# TrinketBlinkM0H.net
KiCad netlist of a schematic drawn in EAGLE
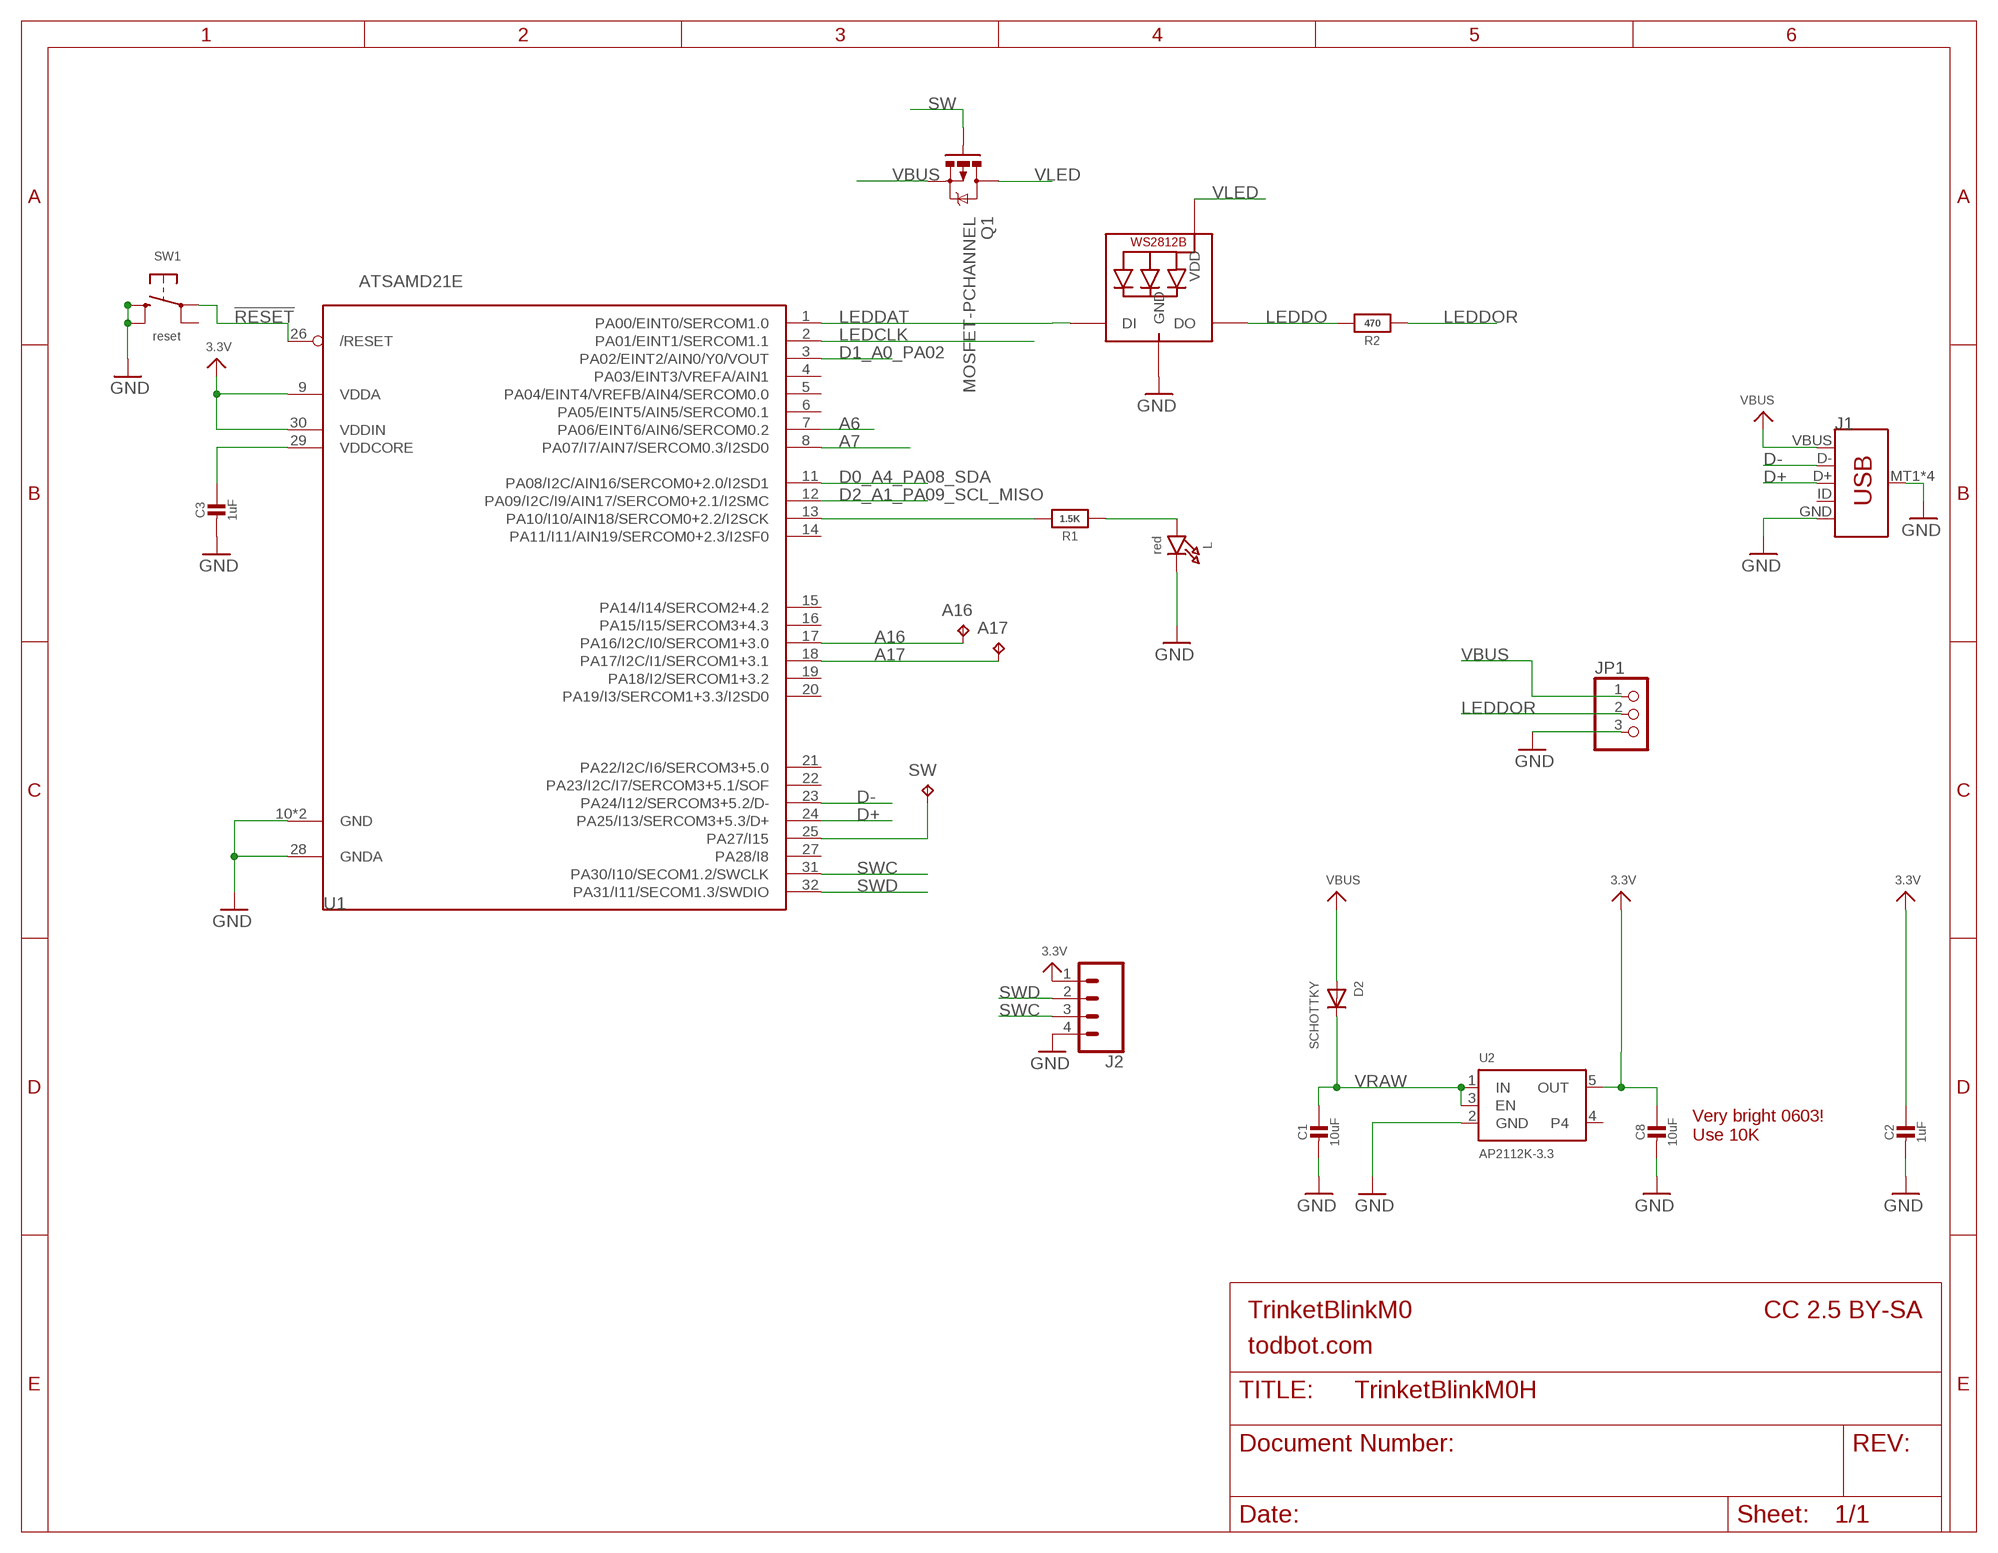
[diagram p0: schematic, sheet 1]

(export (version "E")
  (design (tool "Eeschema 10.0.6"))
  (components
    (comp (ref "A16")
      (value "TPB1,27")
      (footprint "eagle-import:B1,27")
      (libsource (lib "eagle-import") (part "TPB1,27"))
    )
    (comp (ref "A17")
      (value "TPB1,27")
      (footprint "eagle-import:B1,27")
      (libsource (lib "eagle-import") (part "TPB1,27"))
    )
    (comp (ref "C1")
      (value "10uF")
      (footprint "eagle-import:0805-NO")
      (libsource (lib "eagle-import") (part "CAP_CERAMIC0805-NOOUTLINE"))
    )
    (comp (ref "C2")
      (value "1uF")
      (footprint "eagle-import:0603-NO")
      (libsource (lib "eagle-import") (part "CAP_CERAMIC0603_NO"))
    )
    (comp (ref "C3")
      (value "1uF")
      (footprint "eagle-import:0603-NO")
      (libsource (lib "eagle-import") (part "CAP_CERAMIC0603_NO"))
    )
    (comp (ref "C8")
      (value "10uF")
      (footprint "eagle-import:0805-NO")
      (libsource (lib "eagle-import") (part "CAP_CERAMIC0805-NOOUTLINE"))
    )
    (comp (ref "D2")
      (value "SCHOTTKY")
      (footprint "eagle-import:SOD-123FL")
      (libsource (lib "eagle-import") (part "DIODE_SOD-123FL"))
    )
    (comp (ref "J1")
      (value "USB_MICRO-B_SMT")
      (footprint "eagle-import:USB-MICROB")
      (libsource (lib "eagle-import") (part "USB_MICRO-B_SMT"))
    )
    (comp (ref "J2")
      (value "CONN_04")
      (footprint "eagle-import:1X04")
      (libsource (lib "eagle-import") (part "CONN_04"))
    )
    (comp (ref "JP1")
      (value "PINHD-1X3CB")
      (footprint "eagle-import:1X03-CLEANBIG")
      (libsource (lib "eagle-import") (part "PINHD-1X3CB"))
    )
    (comp (ref "L")
      (value "red")
      (footprint "eagle-import:CHIPLED_0603_NOOUTLINE")
      (libsource (lib "eagle-import") (part "LED0603_NOOUTLINE"))
    )
    (comp (ref "LED1")
      (value "WS2812B_5050N")
      (footprint "eagle-import:WS2812B-NARROW")
      (libsource (lib "eagle-import") (part "WS2812B_5050N"))
    )
    (comp (ref "Q1")
      (value "MOSFET-PCHANNEL")
      (footprint "eagle-import:SOT23-3")
      (libsource (lib "eagle-import") (part "MOSFET-PCHANNEL"))
    )
    (comp (ref "R1")
      (value "1.5K")
      (footprint "eagle-import:0603-NO")
      (libsource (lib "eagle-import") (part "RESISTOR_0603_NOOUT"))
    )
    (comp (ref "R2")
      (value "470")
      (footprint "eagle-import:0603-NO")
      (libsource (lib "eagle-import") (part "RESISTOR_0603_NOOUT"))
    )
    (comp (ref "SW")
      (value "TPB1,27")
      (footprint "eagle-import:B1,27")
      (libsource (lib "eagle-import") (part "TPB1,27"))
    )
    (comp (ref "SW1")
      (value "reset")
      (footprint "eagle-import:BTN_KMR2_4.6X2.8")
      (libsource (lib "eagle-import") (part "SWITCH_TACT_SMT4.6X2.8"))
    )
    (comp (ref "U1")
      (value "ATSAMD21E")
      (footprint "eagle-import:QFN32_5MM")
      (libsource (lib "eagle-import") (part "ATSAMD21E"))
    )
    (comp (ref "U2")
      (value "AP2112K-3.3")
      (footprint "eagle-import:SOT23-5")
      (libsource (lib "eagle-import") (part "VREG_SOT23-5"))
    )
  )
  (nets
    (net (code "1") (name "/A6") (class "Default")
      (node (ref "U1") (pin "7") (pinfunction "PA06/EINT6/AIN6/SERCOM0.2_7") (pintype "bidirectional"))
    )
    (net (code "2") (name "/A7") (class "Default")
      (node (ref "U1") (pin "8") (pinfunction "PA07/I7/AIN7/SERCOM0.3/I2SD0_8") (pintype "bidirectional"))
    )
    (net (code "3") (name "/A16") (class "Default")
      (node (ref "A16") (pin "TP") (pinfunction "TP_TP") (pintype "input"))
      (node (ref "U1") (pin "17") (pinfunction "PA16/I2C/I0/SERCOM1+3.0_17") (pintype "bidirectional"))
    )
    (net (code "4") (name "/A17") (class "Default")
      (node (ref "A17") (pin "TP") (pinfunction "TP_TP") (pintype "input"))
      (node (ref "U1") (pin "18") (pinfunction "PA17/I2C/I1/SERCOM1+3.1_18") (pintype "bidirectional"))
    )
    (net (code "5") (name "/D+") (class "Default")
      (node (ref "J1") (pin "D+") (pinfunction "D+_D+") (pintype "bidirectional"))
      (node (ref "U1") (pin "24") (pinfunction "PA25/I13/SERCOM3+5.3/D+_24") (pintype "bidirectional"))
    )
    (net (code "6") (name "/D-") (class "Default")
      (node (ref "J1") (pin "D-") (pinfunction "D-_D-") (pintype "bidirectional"))
      (node (ref "U1") (pin "23") (pinfunction "PA24/I12/SERCOM3+5.2/D-_23") (pintype "bidirectional"))
    )
    (net (code "7") (name "/D0_A4_PA08_SDA") (class "Default")
      (node (ref "U1") (pin "11") (pinfunction "PA08/I2C/AIN16/SERCOM0+2.0/I2SD1_11") (pintype "bidirectional"))
    )
    (net (code "8") (name "/D1_A0_PA02") (class "Default")
      (node (ref "U1") (pin "3") (pinfunction "PA02/EINT2/AIN0/Y0/VOUT_3") (pintype "bidirectional"))
    )
    (net (code "9") (name "/D2_A1_PA09_SCL_MISO") (class "Default")
      (node (ref "U1") (pin "12") (pinfunction "PA09/I2C/I9/AIN17/SERCOM0+2.1/I2SMC_12") (pintype "bidirectional"))
    )
    (net (code "10") (name "/LEDCLK") (class "Default")
      (node (ref "U1") (pin "2") (pinfunction "PA01/EINT1/SERCOM1.1_2") (pintype "bidirectional"))
    )
    (net (code "11") (name "/LEDDAT") (class "Default")
      (node (ref "LED1") (pin "4-DIN") (pinfunction "DI_4-DIN") (pintype "input"))
      (node (ref "U1") (pin "1") (pinfunction "PA00/EINT0/SERCOM1.0_1") (pintype "bidirectional"))
    )
    (net (code "12") (name "/LEDDO") (class "Default")
      (node (ref "LED1") (pin "2-DOUT") (pinfunction "DO_2-DOUT") (pintype "output"))
      (node (ref "R2") (pin "2") (pinfunction "2_2") (pintype "passive"))
    )
    (net (code "13") (name "/LEDDOR") (class "Default")
      (node (ref "JP1") (pin "2") (pinfunction "2_2") (pintype "passive"))
      (node (ref "R2") (pin "1") (pinfunction "1_1") (pintype "passive"))
    )
    (net (code "14") (name "/SW") (class "Default")
      (node (ref "Q1") (pin "1") (pinfunction "G_1") (pintype "passive"))
      (node (ref "SW") (pin "TP") (pinfunction "TP_TP") (pintype "input"))
      (node (ref "U1") (pin "25") (pinfunction "PA27/I15_25") (pintype "bidirectional"))
    )
    (net (code "15") (name "/SWC") (class "Default")
      (node (ref "J2") (pin "3") (pinfunction "3_3") (pintype "passive"))
      (node (ref "U1") (pin "31") (pinfunction "PA30/I10/SECOM1.2/SWCLK_31") (pintype "bidirectional"))
    )
    (net (code "16") (name "/SWD") (class "Default")
      (node (ref "J2") (pin "2") (pinfunction "2_2") (pintype "passive"))
      (node (ref "U1") (pin "32") (pinfunction "PA31/I11/SECOM1.3/SWDIO_32") (pintype "bidirectional"))
    )
    (net (code "17") (name "/VLED") (class "Default")
      (node (ref "LED1") (pin "1-VDD") (pinfunction "VDD_1-VDD") (pintype "power_in"))
      (node (ref "Q1") (pin "3") (pinfunction "D_3") (pintype "passive"))
    )
    (net (code "18") (name "/VRAW") (class "Default")
      (node (ref "C1") (pin "1") (pinfunction "1_1") (pintype "passive"))
      (node (ref "D2") (pin "C") (pinfunction "C_C") (pintype "passive"))
      (node (ref "U2") (pin "1") (pinfunction "IN_1") (pintype "power_in"))
      (node (ref "U2") (pin "3") (pinfunction "EN_3") (pintype "input"))
    )
    (net (code "19") (name "/~{RESET}") (class "Default")
      (node (ref "SW1") (pin "A") (pinfunction "P_A") (pintype "passive"))
      (node (ref "U1") (pin "26") (pinfunction "/RESET_26") (pintype "bidirectional"))
    )
    (net (code "20") (name "3.3V") (class "Default")
      (node (ref "C2") (pin "1") (pinfunction "1_1") (pintype "passive"))
      (node (ref "C8") (pin "1") (pinfunction "1_1") (pintype "passive"))
      (node (ref "J2") (pin "1") (pinfunction "1_1") (pintype "passive"))
      (node (ref "U1") (pin "30") (pinfunction "VDDIN_30") (pintype "power_in"))
      (node (ref "U1") (pin "9") (pinfunction "VDDA_9") (pintype "power_in"))
      (node (ref "U2") (pin "5") (pinfunction "OUT_5") (pintype "power_in"))
    )
    (net (code "21") (name "GND") (class "Default")
      (node (ref "C1") (pin "2") (pinfunction "2_2") (pintype "passive"))
      (node (ref "C2") (pin "2") (pinfunction "2_2") (pintype "passive"))
      (node (ref "C3") (pin "2") (pinfunction "2_2") (pintype "passive"))
      (node (ref "C8") (pin "2") (pinfunction "2_2") (pintype "passive"))
      (node (ref "J1") (pin "GND") (pinfunction "GND_GND") (pintype "power_in"))
      (node (ref "J1") (pin "MT1") (pinfunction "SHIELD_MT1") (pintype "bidirectional"))
      (node (ref "J1") (pin "MT2") (pinfunction "SHIELD_MT2") (pintype "bidirectional"))
      (node (ref "J1") (pin "P$1") (pinfunction "SHIELD_P$1") (pintype "bidirectional"))
      (node (ref "J1") (pin "P$2") (pinfunction "SHIELD_P$2") (pintype "bidirectional"))
      (node (ref "J2") (pin "4") (pinfunction "4_4") (pintype "passive"))
      (node (ref "JP1") (pin "3") (pinfunction "3_3") (pintype "passive"))
      (node (ref "L") (pin "C") (pinfunction "C_C") (pintype "passive"))
      (node (ref "LED1") (pin "3-GND") (pinfunction "GND_3-GND") (pintype "power_in"))
      (node (ref "SW1") (pin "B") (pinfunction "S_B") (pintype "passive"))
      (node (ref "SW1") (pin "B'") (pinfunction "S1_B'") (pintype "passive"))
      (node (ref "U1") (pin "10") (pinfunction "GND_10") (pintype "power_in"))
      (node (ref "U1") (pin "28") (pinfunction "GNDA_28") (pintype "power_in"))
      (node (ref "U1") (pin "33") (pinfunction "GND_33") (pintype "power_in"))
      (node (ref "U2") (pin "2") (pinfunction "GND_2") (pintype "power_in"))
    )
    (net (code "22") (name "Net-(L-PadA)") (class "Default")
      (node (ref "L") (pin "A") (pinfunction "A_A") (pintype "passive"))
      (node (ref "R1") (pin "1") (pinfunction "1_1") (pintype "passive"))
    )
    (net (code "23") (name "Net-(U1-PA10{slash}I10{slash}AIN18{slash}SERCOM0+2.2{slash}I2SCK)") (class "Default")
      (node (ref "R1") (pin "2") (pinfunction "2_2") (pintype "passive"))
      (node (ref "U1") (pin "13") (pinfunction "PA10/I10/AIN18/SERCOM0+2.2/I2SCK_13") (pintype "bidirectional"))
    )
    (net (code "24") (name "Net-(U1-VDDCORE)") (class "Default")
      (node (ref "C3") (pin "1") (pinfunction "1_1") (pintype "passive"))
      (node (ref "U1") (pin "29") (pinfunction "VDDCORE_29") (pintype "power_in"))
    )
    (net (code "25") (name "VBUS") (class "Default")
      (node (ref "D2") (pin "A") (pinfunction "A_A") (pintype "passive"))
      (node (ref "J1") (pin "VBUS") (pinfunction "VBUS_VBUS") (pintype "power_in"))
      (node (ref "JP1") (pin "1") (pinfunction "1_1") (pintype "passive"))
      (node (ref "Q1") (pin "2") (pinfunction "S_2") (pintype "passive"))
    )
    (net (code "26") (name "unconnected-(J1-PadID)") (class "Default")
      (node (ref "J1") (pin "ID") (pinfunction "ID_ID") (pintype "bidirectional"))
    )
    (net (code "27") (name "unconnected-(SW1-P1-PadA')") (class "Default")
      (node (ref "SW1") (pin "A'") (pinfunction "P1_A'") (pintype "passive"))
    )
    (net (code "28") (name "unconnected-(U1-PA03{slash}EINT3{slash}VREFA{slash}AIN1-Pad4)") (class "Default")
      (node (ref "U1") (pin "4") (pinfunction "PA03/EINT3/VREFA/AIN1_4") (pintype "bidirectional"))
    )
    (net (code "29") (name "unconnected-(U1-PA04{slash}EINT4{slash}VREFB{slash}AIN4{slash}SERCOM0.0-Pad5)") (class "Default")
      (node (ref "U1") (pin "5") (pinfunction "PA04/EINT4/VREFB/AIN4/SERCOM0.0_5") (pintype "bidirectional"))
    )
    (net (code "30") (name "unconnected-(U1-PA05{slash}EINT5{slash}AIN5{slash}SERCOM0.1-Pad6)") (class "Default")
      (node (ref "U1") (pin "6") (pinfunction "PA05/EINT5/AIN5/SERCOM0.1_6") (pintype "bidirectional"))
    )
    (net (code "31") (name "unconnected-(U1-PA11{slash}I11{slash}AIN19{slash}SERCOM0+2.3{slash}I2SF0-Pad14)") (class "Default")
      (node (ref "U1") (pin "14") (pinfunction "PA11/I11/AIN19/SERCOM0+2.3/I2SF0_14") (pintype "bidirectional"))
    )
    (net (code "32") (name "unconnected-(U1-PA14{slash}I14{slash}SERCOM2+4.2-Pad15)") (class "Default")
      (node (ref "U1") (pin "15") (pinfunction "PA14/I14/SERCOM2+4.2_15") (pintype "bidirectional"))
    )
    (net (code "33") (name "unconnected-(U1-PA15{slash}I15{slash}SERCOM3+4.3-Pad16)") (class "Default")
      (node (ref "U1") (pin "16") (pinfunction "PA15/I15/SERCOM3+4.3_16") (pintype "bidirectional"))
    )
    (net (code "34") (name "unconnected-(U1-PA18{slash}I2{slash}SERCOM1+3.2-Pad19)") (class "Default")
      (node (ref "U1") (pin "19") (pinfunction "PA18/I2/SERCOM1+3.2_19") (pintype "bidirectional"))
    )
    (net (code "35") (name "unconnected-(U1-PA19{slash}I3{slash}SERCOM1+3.3{slash}I2SD0-Pad20)") (class "Default")
      (node (ref "U1") (pin "20") (pinfunction "PA19/I3/SERCOM1+3.3/I2SD0_20") (pintype "bidirectional"))
    )
    (net (code "36") (name "unconnected-(U1-PA22{slash}I2C{slash}I6{slash}SERCOM3+5.0-Pad21)") (class "Default")
      (node (ref "U1") (pin "21") (pinfunction "PA22/I2C/I6/SERCOM3+5.0_21") (pintype "bidirectional"))
    )
    (net (code "37") (name "unconnected-(U1-PA23{slash}I2C{slash}I7{slash}SERCOM3+5.1{slash}SOF-Pad22)") (class "Default")
      (node (ref "U1") (pin "22") (pinfunction "PA23/I2C/I7/SERCOM3+5.1/SOF_22") (pintype "bidirectional"))
    )
    (net (code "38") (name "unconnected-(U1-PA28{slash}I8-Pad27)") (class "Default")
      (node (ref "U1") (pin "27") (pinfunction "PA28/I8_27") (pintype "bidirectional"))
    )
    (net (code "39") (name "unconnected-(U2-P4-Pad4)") (class "Default")
      (node (ref "U2") (pin "4") (pinfunction "P4_4") (pintype "bidirectional"))
    )
  )
)
